# SOL_ZSAT_lora.net
KiCad netlist of a schematic drawn in EAGLE
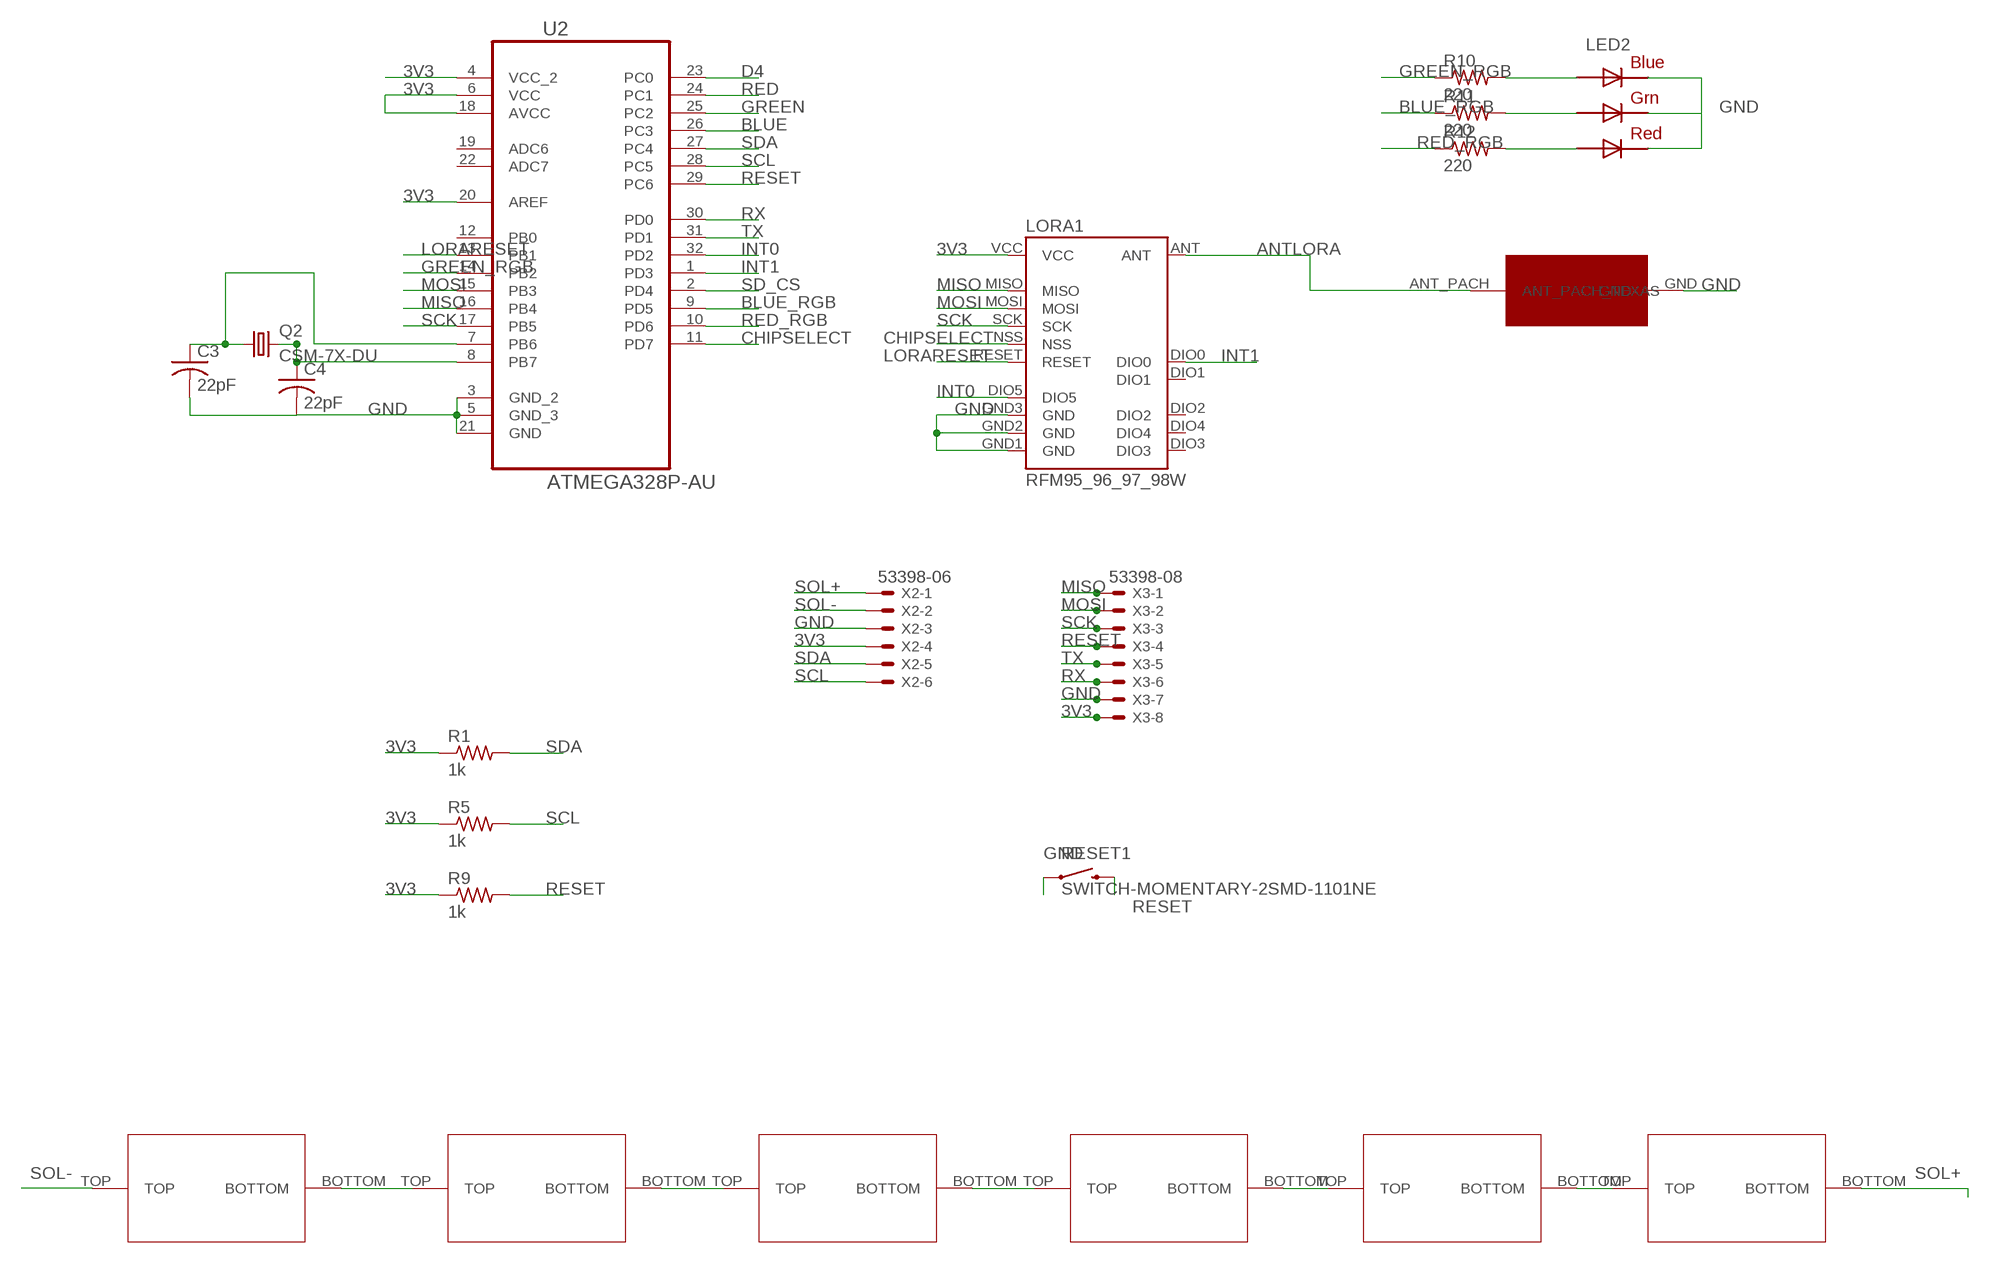
[diagram p0: schematic, sheet 1]

(export (version "E")
  (design (tool "Eeschema 10.0.6"))
  (components
    (comp (ref "C3")
      (value "22pF")
      (footprint "eagle-import:C0603")
      (libsource (lib "eagle-import") (part "C-USC0603"))
    )
    (comp (ref "C4")
      (value "22pF")
      (footprint "eagle-import:C0603")
      (libsource (lib "eagle-import") (part "C-USC0603"))
    )
    (comp (ref "LED2")
      (value "RGBLED5050")
      (footprint "eagle-import:RGBLED5050")
      (libsource (lib "eagle-import") (part "RGBLED5050"))
    )
    (comp (ref "LORA1")
      (value "RFM95_96_97_98W")
      (footprint "eagle-import:RFM95_96_97_98W")
      (libsource (lib "eagle-import") (part "RFM95_96_97_98W"))
    )
    (comp (ref "Q2")
      (value "CSM-7X-DU")
      (footprint "eagle-import:CSM-7X-DU")
      (libsource (lib "eagle-import") (part "CSM-7X-DU"))
    )
    (comp (ref "R1")
      (value "1k")
      (footprint "eagle-import:M1206")
      (libsource (lib "eagle-import") (part "R-US_M1206"))
    )
    (comp (ref "R5")
      (value "1k")
      (footprint "eagle-import:M1206")
      (libsource (lib "eagle-import") (part "R-US_M1206"))
    )
    (comp (ref "R9")
      (value "1k")
      (footprint "eagle-import:M1206")
      (libsource (lib "eagle-import") (part "R-US_M1206"))
    )
    (comp (ref "R10")
      (value "220")
      (footprint "eagle-import:R0603")
      (libsource (lib "eagle-import") (part "R-US_R0603"))
    )
    (comp (ref "R11")
      (value "220")
      (footprint "eagle-import:R0603")
      (libsource (lib "eagle-import") (part "R-US_R0603"))
    )
    (comp (ref "R12")
      (value "220")
      (footprint "eagle-import:R0603")
      (libsource (lib "eagle-import") (part "R-US_R0603"))
    )
    (comp (ref "RESET1")
      (value "SWITCH-MOMENTARY-2SMD-1101NE")
      (footprint "eagle-import:TACTILE-SWITCH-1101NE")
      (libsource (lib "eagle-import") (part "SWITCH-MOMENTARY-2SMD-1101NE"))
    )
    (comp (ref "U$1")
      (value "SOL_26X52")
      (footprint "eagle-import:SOLAR_52X26")
      (libsource (lib "eagle-import") (part "SOL_26X52"))
    )
    (comp (ref "U$2")
      (value "SOL_26X52")
      (footprint "eagle-import:SOLAR_52X26")
      (libsource (lib "eagle-import") (part "SOL_26X52"))
    )
    (comp (ref "U$3")
      (value "SOL_26X52")
      (footprint "eagle-import:SOLAR_52X26")
      (libsource (lib "eagle-import") (part "SOL_26X52"))
    )
    (comp (ref "U$4")
      (value "SOL_26X52")
      (footprint "eagle-import:SOLAR_52X26")
      (libsource (lib "eagle-import") (part "SOL_26X52"))
    )
    (comp (ref "U$5")
      (value "SOL_26X52")
      (footprint "eagle-import:SOLAR_52X26")
      (libsource (lib "eagle-import") (part "SOL_26X52"))
    )
    (comp (ref "U$6")
      (value "SOL_26X52")
      (footprint "eagle-import:SOLAR_52X26")
      (libsource (lib "eagle-import") (part "SOL_26X52"))
    )
    (comp (ref "U$7")
      (value "915MHZ_PACH_TEXAS")
      (footprint "eagle-import:915MHZ_PACH_TEXAS")
      (libsource (lib "eagle-import") (part "915MHZ_PACH_TEXAS"))
    )
    (comp (ref "U2")
      (value "ATMEGA328P-AU")
      (footprint "eagle-import:QFP80P900X900X120-32N")
      (libsource (lib "eagle-import") (part "ATMEGA328P-AU"))
    )
    (comp (ref "X2")
      (value "53398-06")
      (footprint "eagle-import:53398-06")
      (fields (field (name "MF") "MOLEX"))
      (libsource (lib "eagle-import") (part "53?-06398"))
    )
    (comp (ref "X3")
      (value "53398-08")
      (footprint "eagle-import:53398-08")
      (fields (field (name "MF") "MOLEX"))
      (libsource (lib "eagle-import") (part "53?-08398"))
    )
  )
  (nets
    (net (code "1") (name "/3V3") (class "Default")
      (node (ref "LORA1") (pin "VCC") (pinfunction "VCC_VCC") (pintype "bidirectional"))
      (node (ref "R1") (pin "1") (pinfunction "1_1") (pintype "passive"))
      (node (ref "R5") (pin "1") (pinfunction "1_1") (pintype "passive"))
      (node (ref "R9") (pin "1") (pinfunction "1_1") (pintype "passive"))
      (node (ref "U2") (pin "18") (pinfunction "AVCC_18") (pintype "power_in"))
      (node (ref "U2") (pin "20") (pinfunction "AREF_20") (pintype "input"))
      (node (ref "U2") (pin "4") (pinfunction "VCC_2_4") (pintype "power_in"))
      (node (ref "U2") (pin "6") (pinfunction "VCC_6") (pintype "power_in"))
      (node (ref "X2") (pin "4") (pinfunction "S_4") (pintype "passive"))
      (node (ref "X3") (pin "8") (pinfunction "S_8") (pintype "passive"))
    )
    (net (code "2") (name "/ANTLORA") (class "Default")
      (node (ref "LORA1") (pin "ANT") (pinfunction "ANT_ANT") (pintype "bidirectional"))
      (node (ref "U$7") (pin "ANT_PACH") (pinfunction "ANT_PACH_TEXAS_ANT_PACH") (pintype "bidirectional"))
    )
    (net (code "3") (name "/BLUE") (class "Default")
      (node (ref "U2") (pin "26") (pinfunction "PC3_26") (pintype "bidirectional"))
    )
    (net (code "4") (name "/BLUE_RGB") (class "Default")
      (node (ref "R11") (pin "1") (pinfunction "1_1") (pintype "passive"))
      (node (ref "U2") (pin "9") (pinfunction "PD5_9") (pintype "bidirectional"))
    )
    (net (code "5") (name "/CHIPSELECT") (class "Default")
      (node (ref "LORA1") (pin "NSS") (pinfunction "NSS_NSS") (pintype "input"))
      (node (ref "U2") (pin "11") (pinfunction "PD7_11") (pintype "bidirectional"))
    )
    (net (code "6") (name "/D4") (class "Default")
      (node (ref "U2") (pin "23") (pinfunction "PC0_23") (pintype "bidirectional"))
    )
    (net (code "7") (name "/GND") (class "Default")
      (node (ref "C3") (pin "2") (pinfunction "2_2") (pintype "passive"))
      (node (ref "C4") (pin "2") (pinfunction "2_2") (pintype "passive"))
      (node (ref "LED2") (pin "4") (pinfunction "BLUE_C_4") (pintype "bidirectional"))
      (node (ref "LED2") (pin "5") (pinfunction "RED_C_5") (pintype "bidirectional"))
      (node (ref "LED2") (pin "6") (pinfunction "GREEN_C_6") (pintype "bidirectional"))
      (node (ref "LORA1") (pin "GND1") (pinfunction "GND_GND1") (pintype "power_in"))
      (node (ref "LORA1") (pin "GND2") (pinfunction "GND_GND2") (pintype "power_in"))
      (node (ref "LORA1") (pin "GND3") (pinfunction "GND_GND3") (pintype "power_in"))
      (node (ref "RESET1") (pin "1") (pinfunction "1_1") (pintype "passive"))
      (node (ref "U$7") (pin "GND") (pinfunction "GND_GND") (pintype "bidirectional"))
      (node (ref "U2") (pin "21") (pinfunction "GND_21") (pintype "passive"))
      (node (ref "U2") (pin "3") (pinfunction "GND_2_3") (pintype "passive"))
      (node (ref "U2") (pin "5") (pinfunction "GND_3_5") (pintype "passive"))
      (node (ref "X2") (pin "3") (pinfunction "S_3") (pintype "passive"))
      (node (ref "X3") (pin "7") (pinfunction "S_7") (pintype "passive"))
    )
    (net (code "8") (name "/GREEN") (class "Default")
      (node (ref "U2") (pin "25") (pinfunction "PC2_25") (pintype "bidirectional"))
    )
    (net (code "9") (name "/GREEN_RGB") (class "Default")
      (node (ref "R10") (pin "1") (pinfunction "1_1") (pintype "passive"))
      (node (ref "U2") (pin "14") (pinfunction "PB2_14") (pintype "bidirectional"))
    )
    (net (code "10") (name "/INT0") (class "Default")
      (node (ref "LORA1") (pin "DIO5") (pinfunction "DIO5_DIO5") (pintype "input"))
      (node (ref "U2") (pin "32") (pinfunction "PD2_32") (pintype "bidirectional"))
    )
    (net (code "11") (name "/INT1") (class "Default")
      (node (ref "LORA1") (pin "DIO0") (pinfunction "DIO0_DIO0") (pintype "input"))
      (node (ref "U2") (pin "1") (pinfunction "PD3_1") (pintype "bidirectional"))
    )
    (net (code "12") (name "/LORARESET") (class "Default")
      (node (ref "LORA1") (pin "RESET") (pinfunction "RESET_RESET") (pintype "output"))
      (node (ref "U2") (pin "13") (pinfunction "PB1_13") (pintype "bidirectional"))
    )
    (net (code "13") (name "/MISO") (class "Default")
      (node (ref "LORA1") (pin "MISO") (pinfunction "MISO_MISO") (pintype "output"))
      (node (ref "U2") (pin "16") (pinfunction "PB4_16") (pintype "bidirectional"))
      (node (ref "X3") (pin "1") (pinfunction "S_1") (pintype "passive"))
    )
    (net (code "14") (name "/MOSI") (class "Default")
      (node (ref "LORA1") (pin "MOSI") (pinfunction "MOSI_MOSI") (pintype "input"))
      (node (ref "U2") (pin "15") (pinfunction "PB3_15") (pintype "bidirectional"))
      (node (ref "X3") (pin "2") (pinfunction "S_2") (pintype "passive"))
    )
    (net (code "15") (name "/RED") (class "Default")
      (node (ref "U2") (pin "24") (pinfunction "PC1_24") (pintype "bidirectional"))
    )
    (net (code "16") (name "/RED_RGB") (class "Default")
      (node (ref "R12") (pin "1") (pinfunction "1_1") (pintype "passive"))
      (node (ref "U2") (pin "10") (pinfunction "PD6_10") (pintype "bidirectional"))
    )
    (net (code "17") (name "/RESET") (class "Default")
      (node (ref "R9") (pin "2") (pinfunction "2_2") (pintype "passive"))
      (node (ref "RESET1") (pin "2") (pinfunction "2_2") (pintype "passive"))
      (node (ref "U2") (pin "29") (pinfunction "PC6_29") (pintype "bidirectional"))
      (node (ref "X3") (pin "4") (pinfunction "S_4") (pintype "passive"))
    )
    (net (code "18") (name "/RX") (class "Default")
      (node (ref "U2") (pin "30") (pinfunction "PD0_30") (pintype "bidirectional"))
      (node (ref "X3") (pin "6") (pinfunction "S_6") (pintype "passive"))
    )
    (net (code "19") (name "/SCK") (class "Default")
      (node (ref "LORA1") (pin "SCK") (pinfunction "SCK_SCK") (pintype "input"))
      (node (ref "U2") (pin "17") (pinfunction "PB5_17") (pintype "bidirectional"))
      (node (ref "X3") (pin "3") (pinfunction "S_3") (pintype "passive"))
    )
    (net (code "20") (name "/SCL") (class "Default")
      (node (ref "R5") (pin "2") (pinfunction "2_2") (pintype "passive"))
      (node (ref "U2") (pin "28") (pinfunction "PC5_28") (pintype "bidirectional"))
      (node (ref "X2") (pin "6") (pinfunction "S_6") (pintype "passive"))
    )
    (net (code "21") (name "/SDA") (class "Default")
      (node (ref "R1") (pin "2") (pinfunction "2_2") (pintype "passive"))
      (node (ref "U2") (pin "27") (pinfunction "PC4_27") (pintype "bidirectional"))
      (node (ref "X2") (pin "5") (pinfunction "S_5") (pintype "passive"))
    )
    (net (code "22") (name "/SD_CS") (class "Default")
      (node (ref "U2") (pin "2") (pinfunction "PD4_2") (pintype "bidirectional"))
    )
    (net (code "23") (name "/SOL+") (class "Default")
      (node (ref "U$6") (pin "BOTTOM") (pinfunction "BOTTOM_BOTTOM") (pintype "bidirectional"))
      (node (ref "X2") (pin "1") (pinfunction "S_1") (pintype "passive"))
    )
    (net (code "24") (name "/SOL-") (class "Default")
      (node (ref "U$1") (pin "TOP") (pinfunction "TOP_TOP") (pintype "bidirectional"))
      (node (ref "X2") (pin "2") (pinfunction "S_2") (pintype "passive"))
    )
    (net (code "25") (name "/TX") (class "Default")
      (node (ref "U2") (pin "31") (pinfunction "PD1_31") (pintype "bidirectional"))
      (node (ref "X3") (pin "5") (pinfunction "S_5") (pintype "passive"))
    )
    (net (code "26") (name "Net-(LED2-BLUE_A)") (class "Default")
      (node (ref "LED2") (pin "3") (pinfunction "BLUE_A_3") (pintype "bidirectional"))
      (node (ref "R10") (pin "2") (pinfunction "2_2") (pintype "passive"))
    )
    (net (code "27") (name "Net-(LED2-GREEN_A)") (class "Default")
      (node (ref "LED2") (pin "1") (pinfunction "GREEN_A_1") (pintype "bidirectional"))
      (node (ref "R11") (pin "2") (pinfunction "2_2") (pintype "passive"))
    )
    (net (code "28") (name "Net-(LED2-RED_A)") (class "Default")
      (node (ref "LED2") (pin "2") (pinfunction "RED_A_2") (pintype "bidirectional"))
      (node (ref "R12") (pin "2") (pinfunction "2_2") (pintype "passive"))
    )
    (net (code "29") (name "Net-(U$1-PadBOTTOM)") (class "Default")
      (node (ref "U$1") (pin "BOTTOM") (pinfunction "BOTTOM_BOTTOM") (pintype "bidirectional"))
      (node (ref "U$2") (pin "TOP") (pinfunction "TOP_TOP") (pintype "bidirectional"))
    )
    (net (code "30") (name "Net-(U$2-PadBOTTOM)") (class "Default")
      (node (ref "U$2") (pin "BOTTOM") (pinfunction "BOTTOM_BOTTOM") (pintype "bidirectional"))
      (node (ref "U$3") (pin "TOP") (pinfunction "TOP_TOP") (pintype "bidirectional"))
    )
    (net (code "31") (name "Net-(U$3-PadBOTTOM)") (class "Default")
      (node (ref "U$3") (pin "BOTTOM") (pinfunction "BOTTOM_BOTTOM") (pintype "bidirectional"))
      (node (ref "U$4") (pin "TOP") (pinfunction "TOP_TOP") (pintype "bidirectional"))
    )
    (net (code "32") (name "Net-(U$4-PadBOTTOM)") (class "Default")
      (node (ref "U$4") (pin "BOTTOM") (pinfunction "BOTTOM_BOTTOM") (pintype "bidirectional"))
      (node (ref "U$5") (pin "TOP") (pinfunction "TOP_TOP") (pintype "bidirectional"))
    )
    (net (code "33") (name "Net-(U$5-PadBOTTOM)") (class "Default")
      (node (ref "U$5") (pin "BOTTOM") (pinfunction "BOTTOM_BOTTOM") (pintype "bidirectional"))
      (node (ref "U$6") (pin "TOP") (pinfunction "TOP_TOP") (pintype "bidirectional"))
    )
    (net (code "34") (name "Net-(U2-PB6)") (class "Default")
      (node (ref "C3") (pin "1") (pinfunction "1_1") (pintype "passive"))
      (node (ref "Q2") (pin "1") (pinfunction "1_1") (pintype "passive"))
      (node (ref "U2") (pin "7") (pinfunction "PB6_7") (pintype "bidirectional"))
    )
    (net (code "35") (name "Net-(U2-PB7)") (class "Default")
      (node (ref "C4") (pin "1") (pinfunction "1_1") (pintype "passive"))
      (node (ref "Q2") (pin "2") (pinfunction "2_2") (pintype "passive"))
      (node (ref "U2") (pin "8") (pinfunction "PB7_8") (pintype "bidirectional"))
    )
    (net (code "36") (name "unconnected-(LORA1-PadDIO1)") (class "Default")
      (node (ref "LORA1") (pin "DIO1") (pinfunction "DIO1_DIO1") (pintype "input"))
    )
    (net (code "37") (name "unconnected-(LORA1-PadDIO2)") (class "Default")
      (node (ref "LORA1") (pin "DIO2") (pinfunction "DIO2_DIO2") (pintype "bidirectional"))
    )
    (net (code "38") (name "unconnected-(LORA1-PadDIO3)") (class "Default")
      (node (ref "LORA1") (pin "DIO3") (pinfunction "DIO3_DIO3") (pintype "bidirectional"))
    )
    (net (code "39") (name "unconnected-(LORA1-PadDIO4)") (class "Default")
      (node (ref "LORA1") (pin "DIO4") (pinfunction "DIO4_DIO4") (pintype "bidirectional"))
    )
    (net (code "40") (name "unconnected-(U2-ADC6-Pad19)") (class "Default")
      (node (ref "U2") (pin "19") (pinfunction "ADC6_19") (pintype "input"))
    )
    (net (code "41") (name "unconnected-(U2-ADC7-Pad22)") (class "Default")
      (node (ref "U2") (pin "22") (pinfunction "ADC7_22") (pintype "input"))
    )
    (net (code "42") (name "unconnected-(U2-PB0-Pad12)") (class "Default")
      (node (ref "U2") (pin "12") (pinfunction "PB0_12") (pintype "bidirectional"))
    )
  )
)
